# yard-ice-2-toplevel.net
KiCad netlist of a schematic drawn in Altium Designer
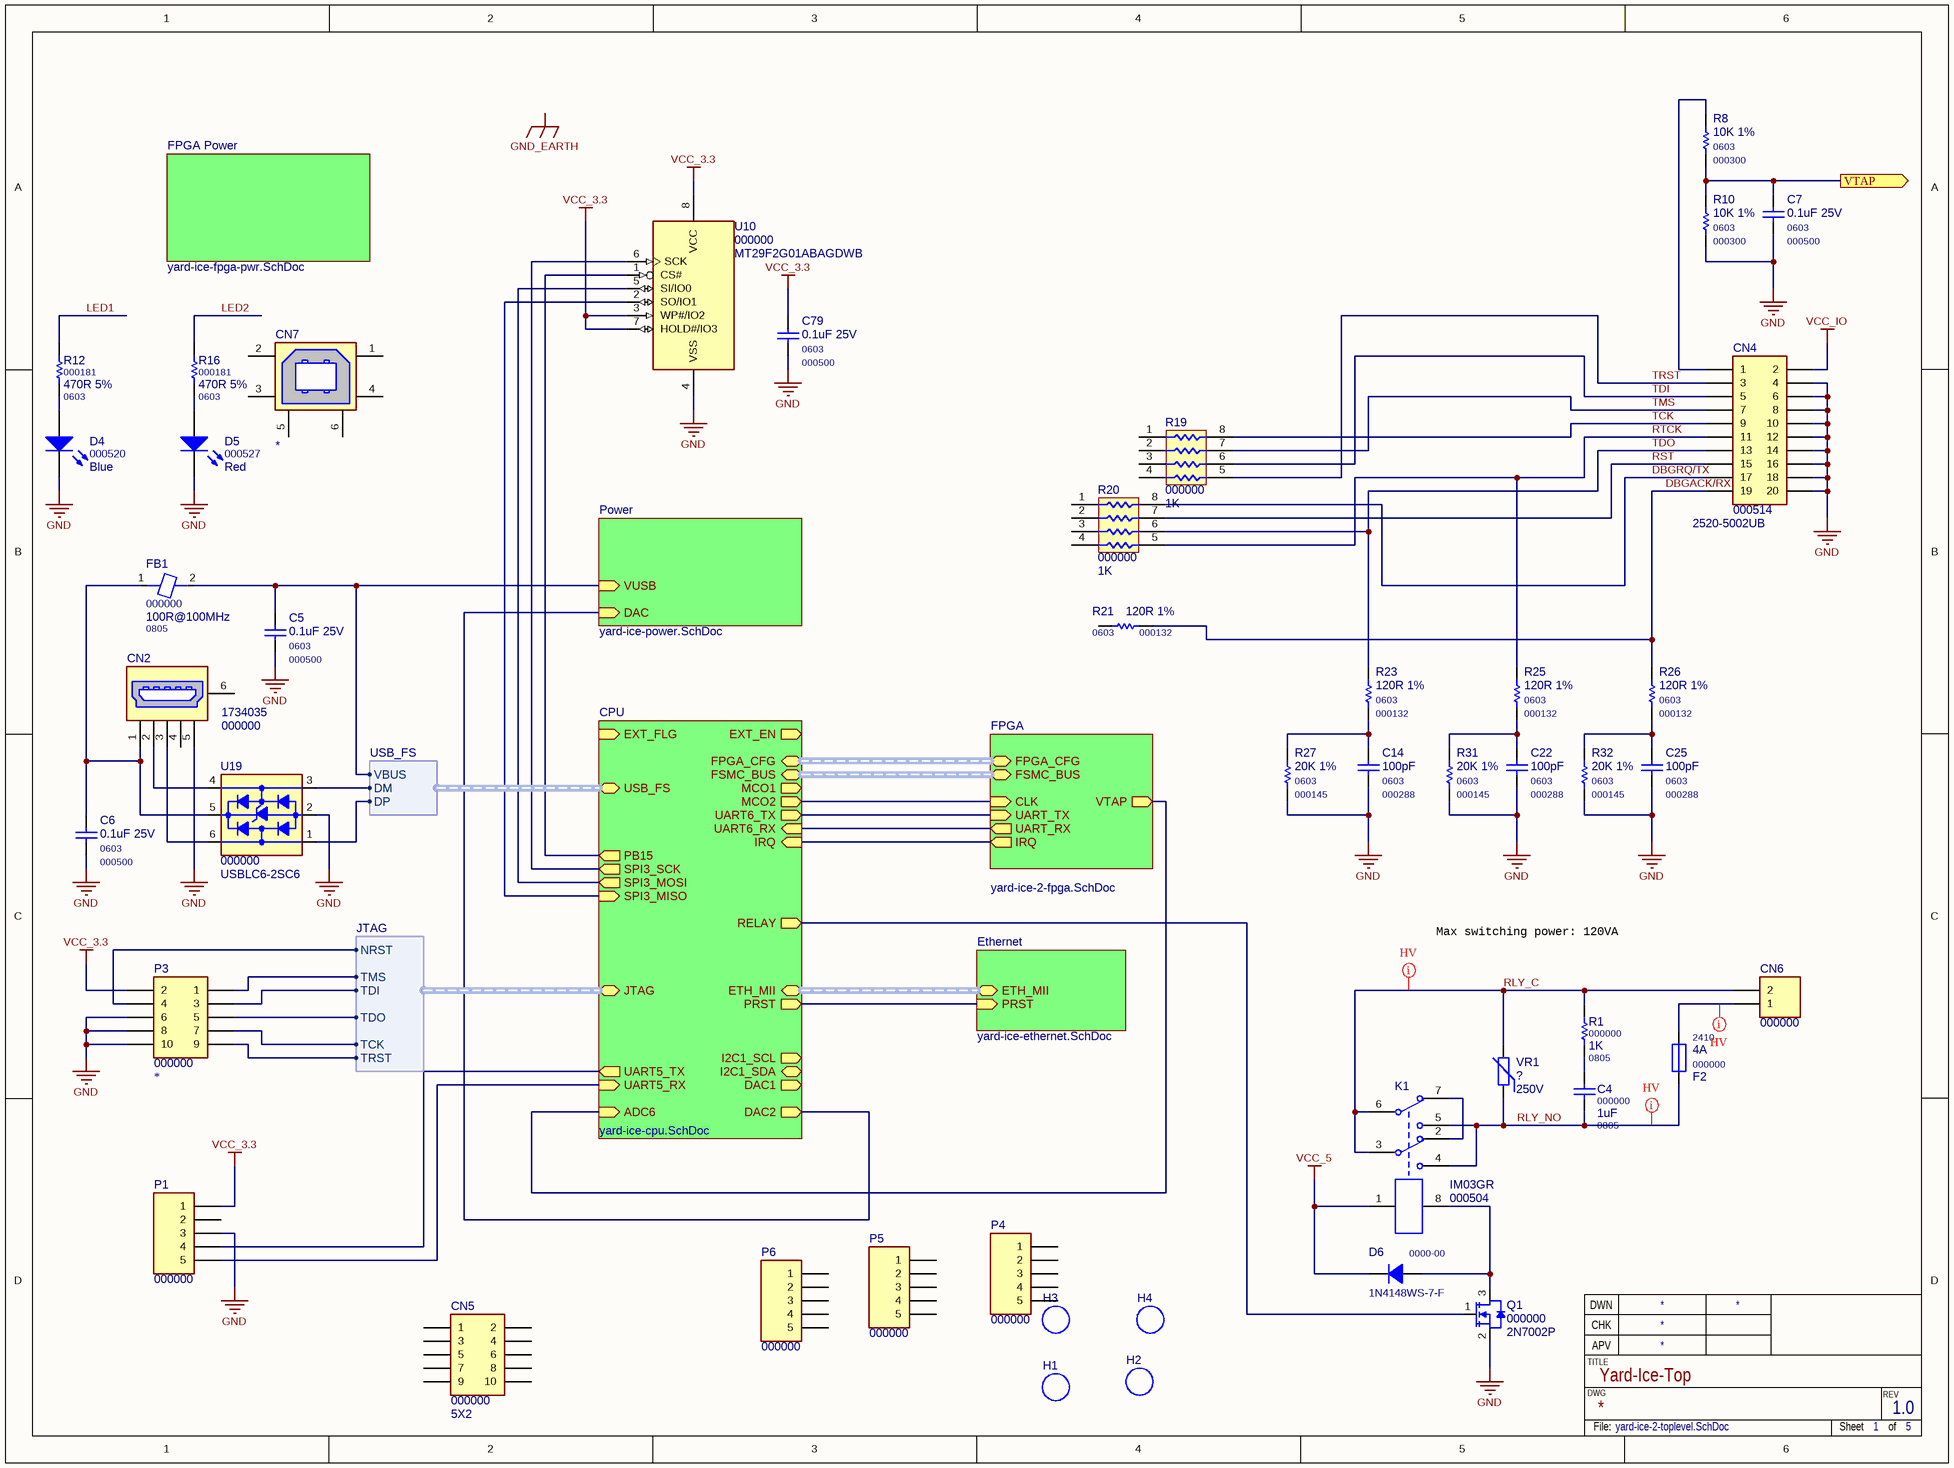
[diagram p0: yard-ice-2-toplevel.SchDoc]

(export (version "E")
  (design (tool "Eeschema 10.0.6"))
  (components
    (comp (ref "C4")
      (value "000000")
      (footprint "C0805HV")
      (description "SMD Ceramic Chip Capacitor - 0805")
      (fields (field (name "ALTIUM_VALUE") "1uF") (field (name "PACKAGE") "0805"))
      (libsource (lib "discrete-sm") (part "C0805"))
    )
    (comp (ref "C5")
      (value "000500")
      (footprint "C0603M")
      (description "SMD Ceramic Chip Capacitor - 0603 - X7R")
      (fields
        (field (name "ALTIUM_VALUE") "0.1uF 25V")
        (field (name "PACKAGE") "0603")
        (field (name "MF") "TDK")
      )
      (libsource (lib "discrete-sm") (part "C0603"))
    )
    (comp (ref "C6")
      (value "000500")
      (footprint "C0603M")
      (description "SMD Ceramic Chip Capacitor - 0603 - X7R")
      (fields
        (field (name "ALTIUM_VALUE") "0.1uF 25V")
        (field (name "PACKAGE") "0603")
        (field (name "MF") "TDK")
      )
      (libsource (lib "discrete-sm") (part "C0603"))
    )
    (comp (ref "C7")
      (value "000500")
      (footprint "C0603M")
      (description "SMD Ceramic Chip Capacitor - 0603 - X7R")
      (fields
        (field (name "ALTIUM_VALUE") "0.1uF 25V")
        (field (name "PACKAGE") "0603")
        (field (name "MF") "TDK")
      )
      (libsource (lib "discrete-sm") (part "C0603"))
    )
    (comp (ref "C14")
      (value "000288")
      (footprint "C0603M")
      (description "SMD Ceramic Chip Capacitor - 0603")
      (fields (field (name "ALTIUM_VALUE") "100pF") (field (name "PACKAGE") "0603"))
      (libsource (lib "discrete-sm") (part "C0603"))
    )
    (comp (ref "C22")
      (value "000288")
      (footprint "C0603M")
      (description "SMD Ceramic Chip Capacitor - 0603")
      (fields (field (name "ALTIUM_VALUE") "100pF") (field (name "PACKAGE") "0603"))
      (libsource (lib "discrete-sm") (part "C0603"))
    )
    (comp (ref "C25")
      (value "000288")
      (footprint "C0603M")
      (description "SMD Ceramic Chip Capacitor - 0603")
      (fields (field (name "ALTIUM_VALUE") "100pF") (field (name "PACKAGE") "0603"))
      (libsource (lib "discrete-sm") (part "C0603"))
    )
    (comp (ref "C79")
      (value "000500")
      (footprint "C0603M")
      (description "SMD Ceramic Chip Capacitor - 0603 - X7R")
      (fields
        (field (name "ALTIUM_VALUE") "0.1uF 25V")
        (field (name "PACKAGE") "0603")
        (field (name "MF") "TDK")
      )
      (libsource (lib "discrete-sm") (part "C0603"))
    )
    (comp (ref "CN2")
      (value "1734035")
      (footprint "1734035")
      (description "USB Type B Mini - Right Angle - SMD")
      (fields (field (name "MF") "Tyco") (field (name "PN") "000000") (field (name "Comment") "000000"))
      (libsource (lib "tyco-conn") (part "1734035"))
    )
    (comp (ref "CN4")
      (value "000514")
      (footprint "TST-110-04-G-D-RA")
      (description "Shrouded Header, 20 Pos, Right Angle")
      (fields (field (name "ALTIUM_VALUE") "2520-5002UB") (field (name "MF") "3M"))
      (libsource (lib "samtec-board-to-board") (part "Header 10X2"))
    )
    (comp (ref "CN5")
      (value "000000")
      (footprint "TST-105-04-G-D-RA")
      (description "Socket 5-Pin, Dual row")
      (fields (field (name "MF") "Samtec") (field (name "ALTIUM_VALUE") "5X2"))
      (libsource (lib "samtec-board-to-board") (part "Header 5X2"))
    )
    (comp (ref "CN6")
      (value "000000")
      (footprint "691322110002")
      (description "Terminal Block, Header, 2-Pos")
      (libsource (lib "wurth") (part "Term Blk 2"))
    )
    (comp (ref "CN7")
      (value "*")
      (footprint "4-1734376")
      (description "USB Type B - Right Angle - Thru Hole")
      (libsource (lib "tyco-conn") (part "4-1734376"))
    )
    (comp (ref "D4")
      (value "000520")
      (footprint "LED0805L LP")
      (description "LED SMD 0805")
      (fields (field (name "ALTIUM_VALUE") "Blue"))
      (libsource (lib "discrete-sm") (part "LED0805LP"))
    )
    (comp (ref "D5")
      (value "000527")
      (footprint "LED0805L LP")
      (description "LED SMD 0805")
      (fields (field (name "ALTIUM_VALUE") "Red"))
      (libsource (lib "discrete-sm") (part "LED0805LP"))
    )
    (comp (ref "D6")
      (value "0000-00")
      (footprint "SOD-323-M")
      (description "Fast Switching Diode 100V 150mA")
      (fields (field (name "MF") "Diodes Inc") (field (name "MF PN") "1N4148WS-7-F"))
      (libsource (lib "diodes-inc") (part "1N4148WS"))
    )
    (comp (ref "F2")
      (value "000000")
      (footprint "F2410")
      (fields (field (name "PACKAGE") "2410") (field (name "ALTIUM_VALUE") "4A"))
      (libsource (lib "discrete-sm") (part "F2410"))
    )
    (comp (ref "FB1")
      (value "000000")
      (footprint "L0805M")
      (description "SMD Chip Ferrite Bead - 0805")
      (fields (field (name "ALTIUM_VALUE") "100R@100MHz") (field (name "PACKAGE") "0805"))
      (libsource (lib "discrete-sm") (part "FB0805"))
    )
    (comp (ref "H1")
      (value "Hole Non Plated")
      (footprint "Hole NP 3.2x5.0x5.0")
      (libsource (lib "mechanical") (part "Hole Non Plated"))
    )
    (comp (ref "H2")
      (value "Hole Non Plated")
      (footprint "Hole NP 3.2x5.0x5.0")
      (libsource (lib "mechanical") (part "Hole Non Plated"))
    )
    (comp (ref "H3")
      (value "Hole Non Plated")
      (footprint "Hole NP 3.2x5.0x5.0")
      (libsource (lib "mechanical") (part "Hole Non Plated"))
    )
    (comp (ref "H4")
      (value "Hole Non Plated")
      (footprint "Hole NP 3.2x5.0x5.0")
      (libsource (lib "mechanical") (part "Hole Non Plated"))
    )
    (comp (ref "K1")
      (value "000504")
      (footprint "Relay-10X6")
      (description "Dual-Pole Dual-Throw Relay")
      (fields (field (name "ALTIUM_VALUE") "IM03GR") (field (name "MF") "Tyco"))
      (libsource (lib "sm-electromechanical") (part "Relay-DPDT"))
    )
    (comp (ref "P1")
      (value "000000")
      (footprint "TSW-105-07-G-S")
      (description "Header, 5-Pin")
      (libsource (lib "samtec-board-to-board") (part "Header 5"))
    )
    (comp (ref "P3")
      (value "000000")
      (footprint "TSW-105-07-G-D")
      (description "Socket 5-Pin, Dual row")
      (fields (field (name "ALTIUM_VALUE") "*"))
      (libsource (lib "samtec-std-hdr") (part "Header 5X2"))
    )
    (comp (ref "P4")
      (value "000000")
      (footprint "TSW-105-07-G-S")
      (description "Header, 5-Pin")
      (libsource (lib "samtec-board-to-board") (part "Header 5"))
    )
    (comp (ref "P5")
      (value "000000")
      (footprint "TSW-105-07-G-S")
      (description "Header, 5-Pin")
      (libsource (lib "samtec-board-to-board") (part "Header 5"))
    )
    (comp (ref "P6")
      (value "000000")
      (footprint "TSW-105-07-G-S")
      (description "Header, 5-Pin")
      (libsource (lib "samtec-board-to-board") (part "Header 5"))
    )
    (comp (ref "Q1")
      (value "000000")
      (footprint "SOT-23-M")
      (description "N-Channel MOSFET 60V 360mA SOT-23")
      (fields (field (name "ALTIUM_VALUE") "2N7002P"))
      (libsource (lib "nxp") (part "2N7002P"))
    )
    (comp (ref "R1")
      (value "000000")
      (footprint "R0805HV")
      (description "SMD Chip Resistor - 0805")
      (fields (field (name "ALTIUM_VALUE") "1K") (field (name "PACKAGE") "0805"))
      (libsource (lib "discrete-sm") (part "R0805"))
    )
    (comp (ref "R8")
      (value "000300")
      (footprint "R0603M")
      (description "SMD Chip Resistor - 0603")
      (fields (field (name "ALTIUM_VALUE") "10K 1%") (field (name "PACKAGE") "0603"))
      (libsource (lib "discrete-sm") (part "R0603"))
    )
    (comp (ref "R10")
      (value "000300")
      (footprint "R0603M")
      (description "SMD Chip Resistor - 0603")
      (fields (field (name "ALTIUM_VALUE") "10K 1%") (field (name "PACKAGE") "0603"))
      (libsource (lib "discrete-sm") (part "R0603"))
    )
    (comp (ref "R12")
      (value "000181")
      (footprint "R0603M")
      (description "SMD Chip Resistor - 0603")
      (fields (field (name "ALTIUM_VALUE") "470R 5%") (field (name "PACKAGE") "0603"))
      (libsource (lib "discrete-sm") (part "R0603"))
    )
    (comp (ref "R16")
      (value "000181")
      (footprint "R0603M")
      (description "SMD Chip Resistor - 0603")
      (fields (field (name "ALTIUM_VALUE") "470R 5%") (field (name "PACKAGE") "0603"))
      (libsource (lib "discrete-sm") (part "R0603"))
    )
    (comp (ref "R19")
      (value "000000")
      (footprint "R0603x4L")
      (description "SMD Chip Resistor Array - 4x0603")
      (fields (field (name "ALTIUM_VALUE") "1K"))
      (libsource (lib "discrete-sm") (part "R0603x4"))
    )
    (comp (ref "R20")
      (value "000000")
      (footprint "R0603x4L")
      (description "SMD Chip Resistor Array - 4x0603")
      (fields (field (name "ALTIUM_VALUE") "1K"))
      (libsource (lib "discrete-sm") (part "R0603x4"))
    )
    (comp (ref "R21")
      (value "000132")
      (footprint "R0603M")
      (description "SMD Chip Resistor - 0603")
      (fields (field (name "ALTIUM_VALUE") "120R 1%") (field (name "PACKAGE") "0603"))
      (libsource (lib "discrete-sm") (part "R0603"))
    )
    (comp (ref "R23")
      (value "000132")
      (footprint "R0603M")
      (description "SMD Chip Resistor - 0603")
      (fields (field (name "ALTIUM_VALUE") "120R 1%") (field (name "PACKAGE") "0603"))
      (libsource (lib "discrete-sm") (part "R0603"))
    )
    (comp (ref "R25")
      (value "000132")
      (footprint "R0603M")
      (description "SMD Chip Resistor - 0603")
      (fields (field (name "ALTIUM_VALUE") "120R 1%") (field (name "PACKAGE") "0603"))
      (libsource (lib "discrete-sm") (part "R0603"))
    )
    (comp (ref "R26")
      (value "000132")
      (footprint "R0603M")
      (description "SMD Chip Resistor - 0603")
      (fields (field (name "ALTIUM_VALUE") "120R 1%") (field (name "PACKAGE") "0603"))
      (libsource (lib "discrete-sm") (part "R0603"))
    )
    (comp (ref "R27")
      (value "000145")
      (footprint "R0603M")
      (description "SMD Chip Resistor - 0603")
      (fields (field (name "ALTIUM_VALUE") "20K 1%") (field (name "PACKAGE") "0603"))
      (libsource (lib "discrete-sm") (part "R0603"))
    )
    (comp (ref "R31")
      (value "000145")
      (footprint "R0603M")
      (description "SMD Chip Resistor - 0603")
      (fields (field (name "ALTIUM_VALUE") "20K 1%") (field (name "PACKAGE") "0603"))
      (libsource (lib "discrete-sm") (part "R0603"))
    )
    (comp (ref "R32")
      (value "000145")
      (footprint "R0603M")
      (description "SMD Chip Resistor - 0603")
      (fields (field (name "ALTIUM_VALUE") "20K 1%") (field (name "PACKAGE") "0603"))
      (libsource (lib "discrete-sm") (part "R0603"))
    )
    (comp (ref "U10")
      (value "000000")
      (footprint "U-PDFN-8")
      (description "2Gb NANDl Flash Memory,  133MHz, SPI")
      (fields (field (name "MF") "Micron") (field (name "ALTIUM_VALUE") "MT29F2G01ABAGDWB"))
      (libsource (lib "micron") (part "MT29F2G01ABAGDWB"))
    )
    (comp (ref "U19")
      (value "000000")
      (footprint "SOT23-6L")
      (description "USB ESD Protection")
      (fields (field (name "MF") "STMicroelectronics") (field (name "ALTIUM_VALUE") "USBLC6-2SC6"))
      (libsource (lib "st") (part "USBLC6-2SC6"))
    )
    (comp (ref "VR1")
      (value "?")
      (footprint "MOV7x4.8-5.0")
      (description "Varistor (Voltage-Sensitive Resistor)")
      (fields (field (name "ALTIUM_VALUE") "250V"))
      (libsource (lib "discrete-pth") (part "Varistor"))
    )
  )
  (nets
    (net (code "5") (name "/DBGACK{slash}RX") (class "Default")
      (node (ref "CN4") (pin "19") (pinfunction "19_19") (pintype "passive"))
      (node (ref "R21") (pin "1") (pinfunction "1_1") (pintype "passive"))
      (node (ref "R26") (pin "1") (pinfunction "1_1") (pintype "passive"))
    )
    (net (code "6") (name "/DBGRQ{slash}TX") (class "Default")
      (node (ref "CN4") (pin "17") (pinfunction "17_17") (pintype "passive"))
      (node (ref "R20") (pin "8") (pinfunction "8_8") (pintype "passive"))
    )
    (net (code "15") (name "/LED1") (class "Default")
      (node (ref "R12") (pin "1") (pinfunction "1_1") (pintype "passive"))
    )
    (net (code "16") (name "/LED2") (class "Default")
      (node (ref "R16") (pin "1") (pinfunction "1_1") (pintype "passive"))
    )
    (net (code "19") (name "/PB15") (class "Default")
      (node (ref "U10") (pin "1") (pinfunction "CS#_1") (pintype "input"))
    )
    (net (code "21") (name "/RELAY") (class "Default")
      (node (ref "Q1") (pin "1") (pinfunction "G_1") (pintype "passive"))
    )
    (net (code "22") (name "/RLY_C") (class "Default")
      (node (ref "CN6") (pin "2") (pinfunction "2_2") (pintype "passive"))
      (node (ref "K1") (pin "3") (pinfunction "3_3") (pintype "passive"))
      (node (ref "K1") (pin "6") (pinfunction "6_6") (pintype "passive"))
      (node (ref "R1") (pin "2") (pinfunction "2_2") (pintype "passive"))
      (node (ref "VR1") (pin "2") (pinfunction "2_2") (pintype "passive"))
    )
    (net (code "23") (name "/RLY_NO") (class "Default")
      (node (ref "C4") (pin "2") (pinfunction "2_2") (pintype "passive"))
      (node (ref "F2") (pin "1") (pinfunction "1_1") (pintype "passive"))
      (node (ref "K1") (pin "4") (pinfunction "4_4") (pintype "passive"))
      (node (ref "K1") (pin "5") (pinfunction "5_5") (pintype "passive"))
      (node (ref "VR1") (pin "1") (pinfunction "1_1") (pintype "passive"))
    )
    (net (code "24") (name "/RST") (class "Default")
      (node (ref "CN4") (pin "15") (pinfunction "15_15") (pintype "passive"))
      (node (ref "R20") (pin "7") (pinfunction "7_7") (pintype "passive"))
    )
    (net (code "25") (name "/RTCK") (class "Default")
      (node (ref "CN4") (pin "11") (pinfunction "11_11") (pintype "passive"))
      (node (ref "R20") (pin "5") (pinfunction "5_5") (pintype "passive"))
      (node (ref "R25") (pin "1") (pinfunction "1_1") (pintype "passive"))
    )
    (net (code "26") (name "/SPI3_MISO") (class "Default")
      (node (ref "U10") (pin "2") (pinfunction "SO/IO1_2") (pintype "bidirectional"))
    )
    (net (code "27") (name "/SPI3_MOSI") (class "Default")
      (node (ref "U10") (pin "5") (pinfunction "SI/IO0_5") (pintype "bidirectional"))
    )
    (net (code "28") (name "/SPI3_SCK") (class "Default")
      (node (ref "U10") (pin "6") (pinfunction "SCK_6") (pintype "input"))
    )
    (net (code "29") (name "/TCK") (class "Default")
      (node (ref "CN4") (pin "9") (pinfunction "9_9") (pintype "passive"))
      (node (ref "R19") (pin "8") (pinfunction "8_8") (pintype "passive"))
    )
    (net (code "30") (name "/TDI") (class "Default")
      (node (ref "CN4") (pin "5") (pinfunction "5_5") (pintype "passive"))
      (node (ref "R19") (pin "6") (pinfunction "6_6") (pintype "passive"))
    )
    (net (code "31") (name "/TDO") (class "Default")
      (node (ref "CN4") (pin "13") (pinfunction "13_13") (pintype "passive"))
      (node (ref "R20") (pin "6") (pinfunction "6_6") (pintype "passive"))
      (node (ref "R23") (pin "1") (pinfunction "1_1") (pintype "passive"))
    )
    (net (code "32") (name "/TMS") (class "Default")
      (node (ref "CN4") (pin "7") (pinfunction "7_7") (pintype "passive"))
      (node (ref "R19") (pin "7") (pinfunction "7_7") (pintype "passive"))
    )
    (net (code "33") (name "/TRST") (class "Default")
      (node (ref "CN4") (pin "3") (pinfunction "3_3") (pintype "passive"))
      (node (ref "R19") (pin "5") (pinfunction "5_5") (pintype "passive"))
    )
    (net (code "34") (name "/UART5_RX") (class "Default")
      (node (ref "P1") (pin "5") (pinfunction "5_5") (pintype "passive"))
    )
    (net (code "35") (name "/UART5_TX") (class "Default")
      (node (ref "P1") (pin "4") (pinfunction "4_4") (pintype "passive"))
    )
    (net (code "38") (name "/VTAP") (class "Default")
      (node (ref "C7") (pin "1") (pinfunction "1_1") (pintype "passive"))
      (node (ref "R10") (pin "1") (pinfunction "1_1") (pintype "passive"))
      (node (ref "R8") (pin "2") (pinfunction "2_2") (pintype "passive"))
    )
    (net (code "40") (name "/VUSB") (class "Default")
      (node (ref "C5") (pin "1") (pinfunction "1_1") (pintype "passive"))
      (node (ref "FB1") (pin "2") (pinfunction "2_2") (pintype "passive"))
    )
    (net (code "43") (name "GND") (class "Default")
      (node (ref "C14") (pin "2") (pinfunction "2_2") (pintype "passive"))
      (node (ref "C22") (pin "2") (pinfunction "2_2") (pintype "passive"))
      (node (ref "C25") (pin "2") (pinfunction "2_2") (pintype "passive"))
      (node (ref "C5") (pin "2") (pinfunction "2_2") (pintype "passive"))
      (node (ref "C6") (pin "2") (pinfunction "2_2") (pintype "passive"))
      (node (ref "C7") (pin "2") (pinfunction "2_2") (pintype "passive"))
      (node (ref "C79") (pin "2") (pinfunction "2_2") (pintype "passive"))
      (node (ref "CN2") (pin "5") (pinfunction "SHIELD_5") (pintype "passive"))
      (node (ref "CN4") (pin "10") (pinfunction "10_10") (pintype "passive"))
      (node (ref "CN4") (pin "12") (pinfunction "12_12") (pintype "passive"))
      (node (ref "CN4") (pin "14") (pinfunction "14_14") (pintype "passive"))
      (node (ref "CN4") (pin "16") (pinfunction "16_16") (pintype "passive"))
      (node (ref "CN4") (pin "18") (pinfunction "18_18") (pintype "passive"))
      (node (ref "CN4") (pin "20") (pinfunction "20_20") (pintype "passive"))
      (node (ref "CN4") (pin "4") (pinfunction "4_4") (pintype "passive"))
      (node (ref "CN4") (pin "6") (pinfunction "6_6") (pintype "passive"))
      (node (ref "CN4") (pin "8") (pinfunction "8_8") (pintype "passive"))
      (node (ref "D4") (pin "2") (pinfunction "K_2") (pintype "passive"))
      (node (ref "D5") (pin "2") (pinfunction "K_2") (pintype "passive"))
      (node (ref "P1") (pin "3") (pinfunction "3_3") (pintype "passive"))
      (node (ref "P3") (pin "10") (pinfunction "10_10") (pintype "passive"))
      (node (ref "P3") (pin "6") (pinfunction "6_6") (pintype "passive"))
      (node (ref "P3") (pin "8") (pinfunction "8_8") (pintype "passive"))
      (node (ref "Q1") (pin "2") (pinfunction "S_2") (pintype "passive"))
      (node (ref "R10") (pin "2") (pinfunction "2_2") (pintype "passive"))
      (node (ref "R27") (pin "2") (pinfunction "2_2") (pintype "passive"))
      (node (ref "R31") (pin "2") (pinfunction "2_2") (pintype "passive"))
      (node (ref "R32") (pin "2") (pinfunction "2_2") (pintype "passive"))
      (node (ref "U10") (pin "4") (pinfunction "VSS_4") (pintype "power_in"))
      (node (ref "U19") (pin "2") (pinfunction "GND_2") (pintype "power_in"))
    )
    (net (code "45") (name "Net-(C4-Pad1)") (class "Default")
      (node (ref "C4") (pin "1") (pinfunction "1_1") (pintype "passive"))
      (node (ref "R1") (pin "1") (pinfunction "1_1") (pintype "passive"))
    )
    (net (code "46") (name "Net-(C14-Pad1)") (class "Default")
      (node (ref "C14") (pin "1") (pinfunction "1_1") (pintype "passive"))
      (node (ref "R23") (pin "2") (pinfunction "2_2") (pintype "passive"))
      (node (ref "R27") (pin "1") (pinfunction "1_1") (pintype "passive"))
    )
    (net (code "47") (name "Net-(C22-Pad1)") (class "Default")
      (node (ref "C22") (pin "1") (pinfunction "1_1") (pintype "passive"))
      (node (ref "R25") (pin "2") (pinfunction "2_2") (pintype "passive"))
      (node (ref "R31") (pin "1") (pinfunction "1_1") (pintype "passive"))
    )
    (net (code "48") (name "Net-(C25-Pad1)") (class "Default")
      (node (ref "C25") (pin "1") (pinfunction "1_1") (pintype "passive"))
      (node (ref "R26") (pin "2") (pinfunction "2_2") (pintype "passive"))
      (node (ref "R32") (pin "1") (pinfunction "1_1") (pintype "passive"))
    )
    (net (code "49") (name "Net-(CN4-Pad1)") (class "Default")
      (node (ref "CN4") (pin "1") (pinfunction "1_1") (pintype "passive"))
      (node (ref "R8") (pin "1") (pinfunction "1_1") (pintype "passive"))
    )
    (net (code "50") (name "Net-(CN6-Pad1)") (class "Default")
      (node (ref "CN6") (pin "1") (pinfunction "1_1") (pintype "passive"))
      (node (ref "F2") (pin "2") (pinfunction "2_2") (pintype "passive"))
    )
    (net (code "51") (name "Net-(D4-A)") (class "Default")
      (node (ref "D4") (pin "1") (pinfunction "A_1") (pintype "passive"))
      (node (ref "R12") (pin "2") (pinfunction "2_2") (pintype "passive"))
    )
    (net (code "52") (name "Net-(D5-A)") (class "Default")
      (node (ref "D5") (pin "1") (pinfunction "A_1") (pintype "passive"))
      (node (ref "R16") (pin "2") (pinfunction "2_2") (pintype "passive"))
    )
    (net (code "53") (name "Net-(D6-A)") (class "Default")
      (node (ref "D6") (pin "1") (pinfunction "A_1") (pintype "passive"))
      (node (ref "K1") (pin "8") (pinfunction "8_8") (pintype "passive"))
      (node (ref "Q1") (pin "3") (pinfunction "D_3") (pintype "passive"))
    )
    (net (code "54") (name "Net-(K1-Pad2)") (class "Default")
      (node (ref "K1") (pin "2") (pinfunction "2_2") (pintype "passive"))
      (node (ref "K1") (pin "7") (pinfunction "7_7") (pintype "passive"))
    )
    (net (code "55") (name "Net-(U19-I{slash}O1)") (class "Default")
      (node (ref "CN2") (pin "3") (pinfunction "3_3") (pintype "passive"))
      (node (ref "U19") (pin "6") (pinfunction "I/O1_6") (pintype "open_collector"))
    )
    (net (code "56") (name "Net-(U19-I{slash}O2)") (class "Default")
      (node (ref "CN2") (pin "2") (pinfunction "2_2") (pintype "passive"))
      (node (ref "U19") (pin "4") (pinfunction "I/O2_4") (pintype "open_collector"))
    )
    (net (code "57") (name "Net-(U19-VBUS)") (class "Default")
      (node (ref "C6") (pin "1") (pinfunction "1_1") (pintype "passive"))
      (node (ref "CN2") (pin "1") (pinfunction "1_1") (pintype "passive"))
      (node (ref "FB1") (pin "1") (pinfunction "1_1") (pintype "passive"))
      (node (ref "U19") (pin "5") (pinfunction "VBUS_5") (pintype "power_in"))
    )
    (net (code "58") (name "VCC_3.3") (class "Default")
      (node (ref "C79") (pin "1") (pinfunction "1_1") (pintype "passive"))
      (node (ref "P1") (pin "1") (pinfunction "1_1") (pintype "passive"))
      (node (ref "P3") (pin "2") (pinfunction "2_2") (pintype "passive"))
      (node (ref "U10") (pin "3") (pinfunction "WP#/IO2_3") (pintype "input"))
      (node (ref "U10") (pin "7") (pinfunction "HOLD#/IO3_7") (pintype "bidirectional"))
      (node (ref "U10") (pin "8") (pinfunction "VCC_8") (pintype "power_in"))
    )
    (net (code "59") (name "VCC_5") (class "Default")
      (node (ref "D6") (pin "2") (pinfunction "K_2") (pintype "passive"))
      (node (ref "K1") (pin "1") (pinfunction "1_1") (pintype "passive"))
    )
    (net (code "60") (name "VCC_IO") (class "Default")
      (node (ref "CN4") (pin "2") (pinfunction "2_2") (pintype "passive"))
    )
    (net (code "61") (name "unconnected-(CN2-Pad4)") (class "Default")
      (node (ref "CN2") (pin "4") (pinfunction "4_4") (pintype "passive"))
    )
    (net (code "62") (name "unconnected-(CN2-SHIELD-Pad6)") (class "Default")
      (node (ref "CN2") (pin "6") (pinfunction "SHIELD_6") (pintype "passive"))
    )
    (net (code "63") (name "unconnected-(CN5-Pad1)") (class "Default")
      (node (ref "CN5") (pin "1") (pinfunction "1_1") (pintype "passive"))
    )
    (net (code "64") (name "unconnected-(CN5-Pad2)") (class "Default")
      (node (ref "CN5") (pin "2") (pinfunction "2_2") (pintype "passive"))
    )
    (net (code "65") (name "unconnected-(CN5-Pad3)") (class "Default")
      (node (ref "CN5") (pin "3") (pinfunction "3_3") (pintype "passive"))
    )
    (net (code "66") (name "unconnected-(CN5-Pad4)") (class "Default")
      (node (ref "CN5") (pin "4") (pinfunction "4_4") (pintype "passive"))
    )
    (net (code "67") (name "unconnected-(CN5-Pad5)") (class "Default")
      (node (ref "CN5") (pin "5") (pinfunction "5_5") (pintype "passive"))
    )
    (net (code "68") (name "unconnected-(CN5-Pad6)") (class "Default")
      (node (ref "CN5") (pin "6") (pinfunction "6_6") (pintype "passive"))
    )
    (net (code "69") (name "unconnected-(CN5-Pad7)") (class "Default")
      (node (ref "CN5") (pin "7") (pinfunction "7_7") (pintype "passive"))
    )
    (net (code "70") (name "unconnected-(CN5-Pad8)") (class "Default")
      (node (ref "CN5") (pin "8") (pinfunction "8_8") (pintype "passive"))
    )
    (net (code "71") (name "unconnected-(CN5-Pad9)") (class "Default")
      (node (ref "CN5") (pin "9") (pinfunction "9_9") (pintype "passive"))
    )
    (net (code "72") (name "unconnected-(CN5-Pad10)") (class "Default")
      (node (ref "CN5") (pin "10") (pinfunction "10_10") (pintype "passive"))
    )
    (net (code "73") (name "unconnected-(CN7-Pad1)") (class "Default")
      (node (ref "CN7") (pin "1") (pinfunction "1_1") (pintype "passive"))
    )
    (net (code "74") (name "unconnected-(CN7-Pad2)") (class "Default")
      (node (ref "CN7") (pin "2") (pinfunction "2_2") (pintype "passive"))
    )
    (net (code "75") (name "unconnected-(CN7-Pad3)") (class "Default")
      (node (ref "CN7") (pin "3") (pinfunction "3_3") (pintype "passive"))
    )
    (net (code "76") (name "unconnected-(CN7-Pad4)") (class "Default")
      (node (ref "CN7") (pin "4") (pinfunction "4_4") (pintype "passive"))
    )
    (net (code "77") (name "unconnected-(CN7-SHIELD-Pad5)") (class "Default")
      (node (ref "CN7") (pin "5") (pinfunction "SHIELD_5") (pintype "passive"))
    )
    (net (code "78") (name "unconnected-(CN7-SHIELD-Pad6)") (class "Default")
      (node (ref "CN7") (pin "6") (pinfunction "SHIELD_6") (pintype "passive"))
    )
    (net (code "79") (name "unconnected-(P1-Pad2)") (class "Default")
      (node (ref "P1") (pin "2") (pinfunction "2_2") (pintype "passive"))
    )
    (net (code "80") (name "unconnected-(P3-Pad1)") (class "Default")
      (node (ref "P3") (pin "1") (pinfunction "1_1") (pintype "passive"))
    )
    (net (code "81") (name "unconnected-(P3-Pad3)") (class "Default")
      (node (ref "P3") (pin "3") (pinfunction "3_3") (pintype "passive"))
    )
    (net (code "82") (name "unconnected-(P3-Pad4)") (class "Default")
      (node (ref "P3") (pin "4") (pinfunction "4_4") (pintype "passive"))
    )
    (net (code "83") (name "unconnected-(P3-Pad5)") (class "Default")
      (node (ref "P3") (pin "5") (pinfunction "5_5") (pintype "passive"))
    )
    (net (code "84") (name "unconnected-(P3-Pad7)") (class "Default")
      (node (ref "P3") (pin "7") (pinfunction "7_7") (pintype "passive"))
    )
    (net (code "85") (name "unconnected-(P3-Pad9)") (class "Default")
      (node (ref "P3") (pin "9") (pinfunction "9_9") (pintype "passive"))
    )
    (net (code "86") (name "unconnected-(P4-Pad1)") (class "Default")
      (node (ref "P4") (pin "1") (pinfunction "1_1") (pintype "passive"))
    )
    (net (code "87") (name "unconnected-(P4-Pad2)") (class "Default")
      (node (ref "P4") (pin "2") (pinfunction "2_2") (pintype "passive"))
    )
    (net (code "88") (name "unconnected-(P4-Pad3)") (class "Default")
      (node (ref "P4") (pin "3") (pinfunction "3_3") (pintype "passive"))
    )
    (net (code "89") (name "unconnected-(P4-Pad4)") (class "Default")
      (node (ref "P4") (pin "4") (pinfunction "4_4") (pintype "passive"))
    )
    (net (code "90") (name "unconnected-(P4-Pad5)") (class "Default")
      (node (ref "P4") (pin "5") (pinfunction "5_5") (pintype "passive"))
    )
    (net (code "91") (name "unconnected-(P5-Pad1)") (class "Default")
      (node (ref "P5") (pin "1") (pinfunction "1_1") (pintype "passive"))
    )
    (net (code "92") (name "unconnected-(P5-Pad2)") (class "Default")
      (node (ref "P5") (pin "2") (pinfunction "2_2") (pintype "passive"))
    )
    (net (code "93") (name "unconnected-(P5-Pad3)") (class "Default")
      (node (ref "P5") (pin "3") (pinfunction "3_3") (pintype "passive"))
    )
    (net (code "94") (name "unconnected-(P5-Pad4)") (class "Default")
      (node (ref "P5") (pin "4") (pinfunction "4_4") (pintype "passive"))
    )
    (net (code "95") (name "unconnected-(P5-Pad5)") (class "Default")
      (node (ref "P5") (pin "5") (pinfunction "5_5") (pintype "passive"))
    )
    (net (code "96") (name "unconnected-(P6-Pad1)") (class "Default")
      (node (ref "P6") (pin "1") (pinfunction "1_1") (pintype "passive"))
    )
    (net (code "97") (name "unconnected-(P6-Pad2)") (class "Default")
      (node (ref "P6") (pin "2") (pinfunction "2_2") (pintype "passive"))
    )
    (net (code "98") (name "unconnected-(P6-Pad3)") (class "Default")
      (node (ref "P6") (pin "3") (pinfunction "3_3") (pintype "passive"))
    )
    (net (code "99") (name "unconnected-(P6-Pad4)") (class "Default")
      (node (ref "P6") (pin "4") (pinfunction "4_4") (pintype "passive"))
    )
    (net (code "100") (name "unconnected-(P6-Pad5)") (class "Default")
      (node (ref "P6") (pin "5") (pinfunction "5_5") (pintype "passive"))
    )
    (net (code "101") (name "unconnected-(R19-Pad1)") (class "Default")
      (node (ref "R19") (pin "1") (pinfunction "1_1") (pintype "passive"))
    )
    (net (code "102") (name "unconnected-(R19-Pad2)") (class "Default")
      (node (ref "R19") (pin "2") (pinfunction "2_2") (pintype "passive"))
    )
    (net (code "103") (name "unconnected-(R19-Pad3)") (class "Default")
      (node (ref "R19") (pin "3") (pinfunction "3_3") (pintype "passive"))
    )
    (net (code "104") (name "unconnected-(R19-Pad4)") (class "Default")
      (node (ref "R19") (pin "4") (pinfunction "4_4") (pintype "passive"))
    )
    (net (code "105") (name "unconnected-(R20-Pad1)") (class "Default")
      (node (ref "R20") (pin "1") (pinfunction "1_1") (pintype "passive"))
    )
    (net (code "106") (name "unconnected-(R20-Pad2)") (class "Default")
      (node (ref "R20") (pin "2") (pinfunction "2_2") (pintype "passive"))
    )
    (net (code "107") (name "unconnected-(R20-Pad3)") (class "Default")
      (node (ref "R20") (pin "3") (pinfunction "3_3") (pintype "passive"))
    )
    (net (code "108") (name "unconnected-(R20-Pad4)") (class "Default")
      (node (ref "R20") (pin "4") (pinfunction "4_4") (pintype "passive"))
    )
    (net (code "109") (name "unconnected-(R21-Pad2)") (class "Default")
      (node (ref "R21") (pin "2") (pinfunction "2_2") (pintype "passive"))
    )
    (net (code "110") (name "unconnected-(U19-IO{slash}1-Pad1)") (class "Default")
      (node (ref "U19") (pin "1") (pinfunction "IO/1_1") (pintype "power_in"))
    )
    (net (code "111") (name "unconnected-(U19-IO{slash}2-Pad3)") (class "Default")
      (node (ref "U19") (pin "3") (pinfunction "IO/2_3") (pintype "power_in"))
    )
  )
)
